# RscDroneBadgeMini.net
KiCad netlist of a schematic drawn in EAGLE
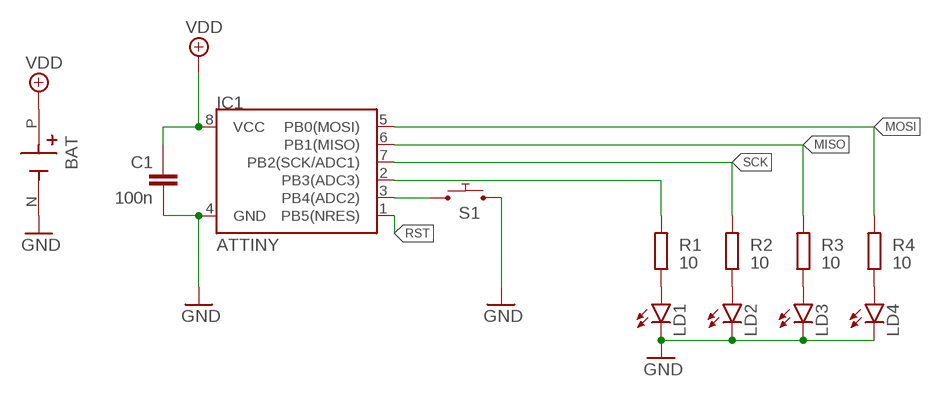
[diagram p0: schematic, sheet 1]

(export (version "E")
  (design (tool "Eeschema 10.0.6"))
  (components
    (comp (ref "BAT")
      (value "CR2032")
      (footprint "eagle-import:CR2032_PLASTIC")
      (libsource (lib "eagle-import") (part "CR2032_PLASTIC"))
    )
    (comp (ref "C1")
      (value "100n")
      (footprint "eagle-import:C_2.54")
      (libsource (lib "eagle-import") (part "CAPACITOR_THT_2.54"))
    )
    (comp (ref "IC1")
      (value "ATTINY")
      (footprint "eagle-import:DIL08")
      (libsource (lib "eagle-import") (part "ATTINY85-20PU"))
    )
    (comp (ref "LD1")
      (value "LED_THT-5MM_NICE")
      (footprint "eagle-import:LED_5MM_NICE")
      (libsource (lib "eagle-import") (part "LED_THT-5MM_NICE"))
    )
    (comp (ref "LD2")
      (value "LED_THT-5MM_NICE")
      (footprint "eagle-import:LED_5MM_NICE")
      (libsource (lib "eagle-import") (part "LED_THT-5MM_NICE"))
    )
    (comp (ref "LD3")
      (value "LED_THT-5MM_NICE")
      (footprint "eagle-import:LED_5MM_NICE")
      (libsource (lib "eagle-import") (part "LED_THT-5MM_NICE"))
    )
    (comp (ref "LD4")
      (value "LED_THT-5MM_NICE")
      (footprint "eagle-import:LED_5MM_NICE")
      (libsource (lib "eagle-import") (part "LED_THT-5MM_NICE"))
    )
    (comp (ref "R1")
      (value "10")
      (footprint "eagle-import:RCL_0207")
      (libsource (lib "eagle-import") (part "RESISTOR_0207_THT0204/7_ROUND"))
    )
    (comp (ref "R2")
      (value "10")
      (footprint "eagle-import:RCL_0207")
      (libsource (lib "eagle-import") (part "RESISTOR_0207_THT0204/7_ROUND"))
    )
    (comp (ref "R3")
      (value "10")
      (footprint "eagle-import:RCL_0207")
      (libsource (lib "eagle-import") (part "RESISTOR_0207_THT0204/7_ROUND"))
    )
    (comp (ref "R4")
      (value "10")
      (footprint "eagle-import:RCL_0207")
      (libsource (lib "eagle-import") (part "RESISTOR_0207_THT0204/7_ROUND"))
    )
    (comp (ref "S1")
      (value "6x6mm BUTTON")
      (footprint "eagle-import:TACTILE-PTH")
      (libsource (lib "eagle-import") (part "PUSH_MOMENTARY_THT_6X6MM"))
    )
  )
  (nets
    (net (code "1") (name "GND") (class "Default")
      (node (ref "BAT") (pin "N") (pinfunction "NEG_N") (pintype "passive"))
      (node (ref "C1") (pin "2") (pinfunction "2_2") (pintype "passive"))
      (node (ref "IC1") (pin "4") (pinfunction "GND_4") (pintype "bidirectional"))
      (node (ref "LD1") (pin "K") (pinfunction "C_K") (pintype "passive"))
      (node (ref "LD2") (pin "K") (pinfunction "C_K") (pintype "passive"))
      (node (ref "LD3") (pin "K") (pinfunction "C_K") (pintype "passive"))
      (node (ref "LD4") (pin "K") (pinfunction "C_K") (pintype "passive"))
      (node (ref "S1") (pin "3") (pinfunction "2_3") (pintype "passive"))
      (node (ref "S1") (pin "4") (pinfunction "2_4") (pintype "passive"))
    )
    (net (code "2") (name "MISO") (class "Default")
      (node (ref "IC1") (pin "6") (pinfunction "PB1(MISO)_6") (pintype "bidirectional"))
      (node (ref "R3") (pin "2") (pinfunction "2_2") (pintype "passive"))
    )
    (net (code "3") (name "MOSI") (class "Default")
      (node (ref "IC1") (pin "5") (pinfunction "PB0(MOSI)_5") (pintype "bidirectional"))
      (node (ref "R4") (pin "2") (pinfunction "2_2") (pintype "passive"))
    )
    (net (code "4") (name "Net-(IC1-PB3(ADC3))") (class "Default")
      (node (ref "IC1") (pin "2") (pinfunction "PB3(ADC3)_2") (pintype "bidirectional"))
      (node (ref "R1") (pin "2") (pinfunction "2_2") (pintype "passive"))
    )
    (net (code "5") (name "Net-(IC1-PB4(ADC2))") (class "Default")
      (node (ref "IC1") (pin "3") (pinfunction "PB4(ADC2)_3") (pintype "bidirectional"))
      (node (ref "S1") (pin "1") (pinfunction "1_1") (pintype "passive"))
      (node (ref "S1") (pin "2") (pinfunction "1_2") (pintype "passive"))
    )
    (net (code "6") (name "Net-(LD1-PadA)") (class "Default")
      (node (ref "LD1") (pin "A") (pinfunction "A_A") (pintype "passive"))
      (node (ref "R1") (pin "1") (pinfunction "1_1") (pintype "passive"))
    )
    (net (code "7") (name "Net-(LD2-PadA)") (class "Default")
      (node (ref "LD2") (pin "A") (pinfunction "A_A") (pintype "passive"))
      (node (ref "R2") (pin "1") (pinfunction "1_1") (pintype "passive"))
    )
    (net (code "8") (name "Net-(LD3-PadA)") (class "Default")
      (node (ref "LD3") (pin "A") (pinfunction "A_A") (pintype "passive"))
      (node (ref "R3") (pin "1") (pinfunction "1_1") (pintype "passive"))
    )
    (net (code "9") (name "Net-(LD4-PadA)") (class "Default")
      (node (ref "LD4") (pin "A") (pinfunction "A_A") (pintype "passive"))
      (node (ref "R4") (pin "1") (pinfunction "1_1") (pintype "passive"))
    )
    (net (code "10") (name "RST") (class "Default")
      (node (ref "IC1") (pin "1") (pinfunction "PB5(NRES)_1") (pintype "bidirectional"))
    )
    (net (code "11") (name "SCK") (class "Default")
      (node (ref "IC1") (pin "7") (pinfunction "PB2(SCK/ADC1)_7") (pintype "bidirectional"))
      (node (ref "R2") (pin "2") (pinfunction "2_2") (pintype "passive"))
    )
    (net (code "12") (name "VDD") (class "Default")
      (node (ref "BAT") (pin "P") (pinfunction "POS_P") (pintype "passive"))
      (node (ref "C1") (pin "1") (pinfunction "1_1") (pintype "passive"))
      (node (ref "IC1") (pin "8") (pinfunction "VCC_8") (pintype "bidirectional"))
    )
  )
)
